# CAN_Sheet.net
KiCad netlist of a schematic drawn in Altium Designer
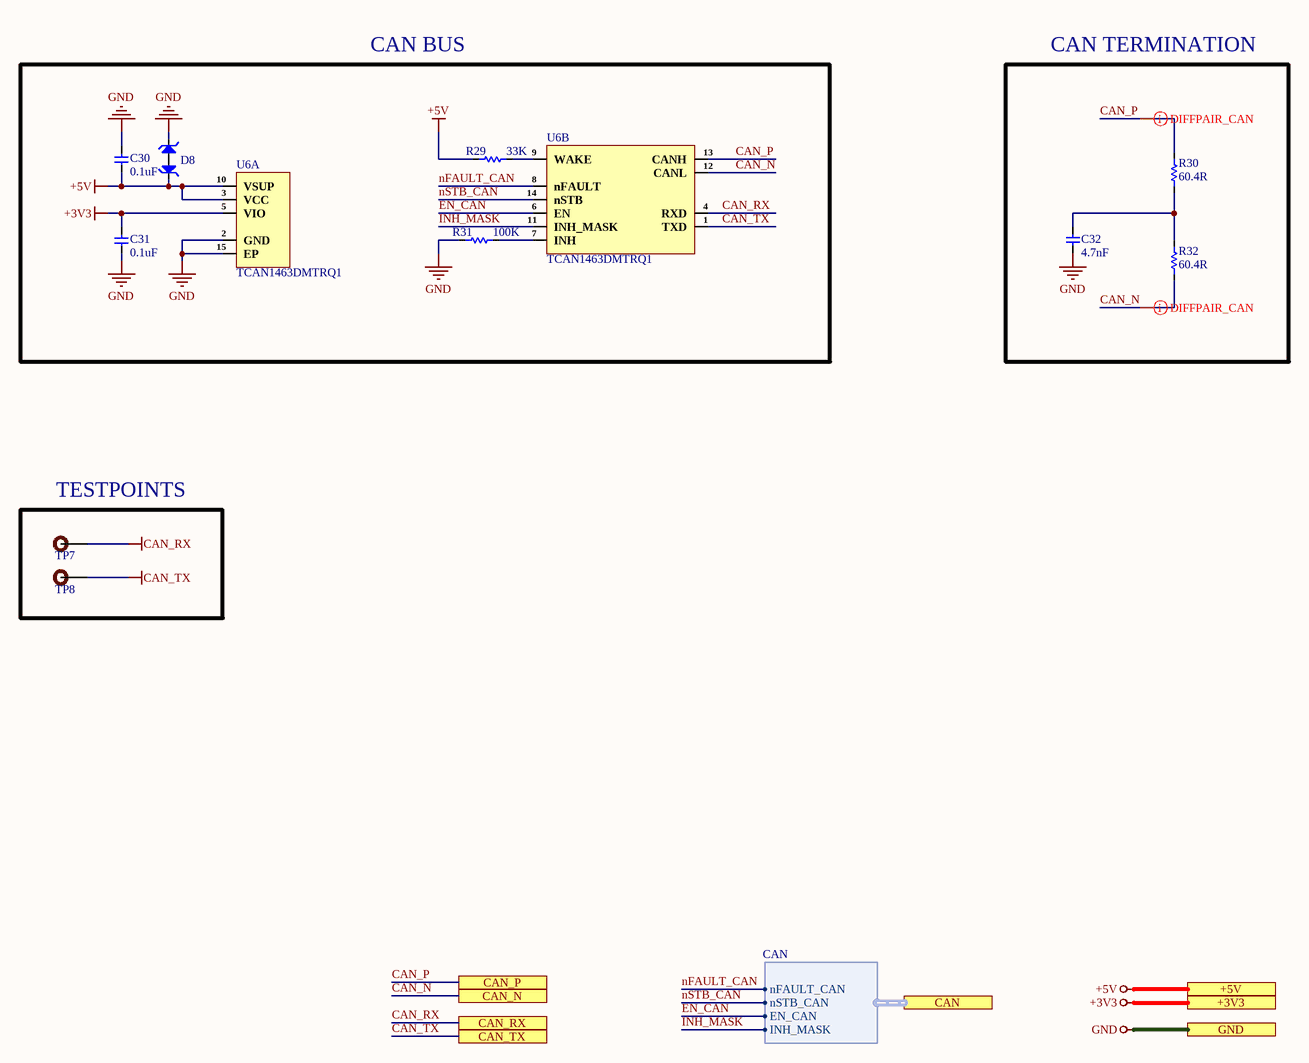
[diagram p0: CAN_Sheet.SchDoc]

(export (version "E")
  (design (tool "Eeschema 10.0.6"))
  (components
    (comp (ref "C30")
      (value "0.1uF")
      (footprint "Cap-0402")
      (description "CAP CER 0.1UF 16V X7R 0402")
      (fields
        (field (name "MANUFACTURER") "Yageo")
        (field (name "MANUFACTURER PART NUMBER") "CC0402JRX7R7BB104")
      )
      (libsource (lib "eSpark Libraries") (part "CC0402JRX7R7BB104"))
    )
    (comp (ref "C31")
      (value "0.1uF")
      (footprint "Cap-0402")
      (description "CAP CER 0.1UF 16V X7R 0402")
      (fields
        (field (name "MANUFACTURER") "Yageo")
        (field (name "MANUFACTURER PART NUMBER") "CC0402JRX7R7BB104")
      )
      (libsource (lib "eSpark Libraries") (part "CC0402JRX7R7BB104"))
    )
    (comp (ref "C32")
      (value "4.7nF")
      (footprint "Cap-0402")
      (description "CAP CER 4700PF 50V X7R 0402")
      (fields
        (field (name "MANUFACTURER") "Yageo")
        (field (name "MANUFACTURER PART NUMBER") "CC0402KRX7R9BB472")
      )
      (libsource (lib "eSpark Libraries") (part "CC0402KRX7R9BB472"))
    )
    (comp (ref "D8")
      (value "PESD5V0H1BSFYL")
      (footprint "DSN0603-2")
      (description "TVS DIODE 5VWM 6.3VC DSN0603-2")
      (fields (field (name "MANUFACTURER") "Nexperia") (field (name "LCSC PART NUMBER") "C477989"))
      (libsource (lib "eSpark Libraries") (part "PESD5V0H1BSFYL"))
    )
    (comp (ref "R29")
      (value "33K")
      (footprint "Res-0402")
      (description "RES 33K OHM 1% 1/16W 0402")
      (fields
        (field (name "MANUFACTURER") "YAGEO")
        (field (name "MANUFACTURER PART NUMBER") "RC0402FR-0733KL")
      )
      (libsource (lib "eSpark Libraries") (part "RC0402FR-0733KL"))
    )
    (comp (ref "R30")
      (value "60.4R")
      (footprint "Res-0603")
      (description "100mW Thick Film Resistors ±100ppm/℃ ±1% 60.4Ω 0603 Chip Resistor - Surface Mount ROHS")
      (fields
        (field (name "MANUFACTURER PART NUMBER") "RTT0360R4FTP")
        (field (name "LCSC PART NUMBER") "C103744")
      )
      (libsource (lib "eSpark Libraries") (part "RTT0360R4FTP"))
    )
    (comp (ref "R31")
      (value "100K")
      (footprint "Res-0402")
      (description "RES 100K OHM 1% 1/16W 0402")
      (fields
        (field (name "MANUFACTURER") "Yageo")
        (field (name "MANUFACTURER PART NUMBER") "RC0402FR-07100KL")
      )
      (libsource (lib "eSpark Libraries") (part "RC0402FR-07100KL"))
    )
    (comp (ref "R32")
      (value "60.4R")
      (footprint "Res-0603")
      (description "100mW Thick Film Resistors ±100ppm/℃ ±1% 60.4Ω 0603 Chip Resistor - Surface Mount ROHS")
      (fields
        (field (name "MANUFACTURER PART NUMBER") "RTT0360R4FTP")
        (field (name "LCSC PART NUMBER") "C103744")
      )
      (libsource (lib "eSpark Libraries") (part "RTT0360R4FTP"))
    )
    (comp (ref "TP7")
      (value "TEST POINT")
      (footprint "Test-point")
      (description "Test Point ON")
      (libsource (lib "eSpark Libraries") (part "TEST POINT"))
    )
    (comp (ref "TP8")
      (value "TEST POINT")
      (footprint "Test-point")
      (description "Test Point ON")
      (libsource (lib "eSpark Libraries") (part "TEST POINT"))
    )
    (comp (ref "U6")
      (value "TCAN1463DMTRQ1")
      (footprint "VSON-14(3x4.5)")
      (description "IC TRANSCEIVER HALF 1/1 14VSON")
      (fields (field (name "MANUFACTURER") "Texas Instruments") (field (name "LCSC PART NUMBER") "C5215823"))
      (libsource (lib "eSpark Libraries") (part "TCAN1463DMTRQ1"))
    )
  )
  (nets
    (net (code "2") (name "+3V3") (class "Default")
      (node (ref "C31") (pin "2") (pinfunction "2_2") (pintype "passive"))
      (node (ref "U6") (pin "5") (pinfunction "VIO_5") (pintype "passive"))
    )
    (net (code "3") (name "+5V") (class "Default")
      (node (ref "C30") (pin "1") (pinfunction "1_1") (pintype "passive"))
      (node (ref "D8") (pin "1") (pinfunction "1_1") (pintype "passive"))
      (node (ref "R29") (pin "1") (pinfunction "1_1") (pintype "passive"))
      (node (ref "U6") (pin "10") (pinfunction "VSUP_10") (pintype "passive"))
      (node (ref "U6") (pin "3") (pinfunction "VCC_3") (pintype "passive"))
    )
    (net (code "4") (name "/CAN_N") (class "Default")
      (node (ref "R32") (pin "2") (pinfunction "2_2") (pintype "passive"))
      (node (ref "U6") (pin "12") (pinfunction "CANL_12") (pintype "passive"))
    )
    (net (code "5") (name "/CAN_P") (class "Default")
      (node (ref "R30") (pin "1") (pinfunction "1_1") (pintype "passive"))
      (node (ref "U6") (pin "13") (pinfunction "CANH_13") (pintype "passive"))
    )
    (net (code "6") (name "/EN_CAN") (class "Default")
      (node (ref "U6") (pin "6") (pinfunction "EN_6") (pintype "passive"))
    )
    (net (code "7") (name "/INH_MASK") (class "Default")
      (node (ref "U6") (pin "11") (pinfunction "INH_MASK_11") (pintype "passive"))
    )
    (net (code "8") (name "/nFAULT_CAN") (class "Default")
      (node (ref "U6") (pin "8") (pinfunction "nFAULT_8") (pintype "passive"))
    )
    (net (code "9") (name "/nSTB_CAN") (class "Default")
      (node (ref "U6") (pin "14") (pinfunction "nSTB_14") (pintype "passive"))
    )
    (net (code "11") (name "CAN_RX") (class "Default")
      (node (ref "TP7") (pin "1") (pinfunction "1_1") (pintype "passive"))
      (node (ref "U6") (pin "4") (pinfunction "RXD_4") (pintype "passive"))
    )
    (net (code "12") (name "CAN_TX") (class "Default")
      (node (ref "TP8") (pin "1") (pinfunction "1_1") (pintype "passive"))
      (node (ref "U6") (pin "1") (pinfunction "TXD_1") (pintype "passive"))
    )
    (net (code "13") (name "GND") (class "Default")
      (node (ref "C30") (pin "2") (pinfunction "2_2") (pintype "passive"))
      (node (ref "C31") (pin "1") (pinfunction "1_1") (pintype "passive"))
      (node (ref "C32") (pin "2") (pinfunction "2_2") (pintype "passive"))
      (node (ref "D8") (pin "2") (pinfunction "2_2") (pintype "passive"))
      (node (ref "R31") (pin "1") (pinfunction "1_1") (pintype "passive"))
      (node (ref "U6") (pin "15") (pinfunction "EP_15") (pintype "passive"))
      (node (ref "U6") (pin "2") (pinfunction "GND_2") (pintype "passive"))
    )
    (net (code "14") (name "Net-(C32-Pad1)") (class "Default")
      (node (ref "C32") (pin "1") (pinfunction "1_1") (pintype "passive"))
      (node (ref "R30") (pin "2") (pinfunction "2_2") (pintype "passive"))
      (node (ref "R32") (pin "1") (pinfunction "1_1") (pintype "passive"))
    )
    (net (code "15") (name "Net-(U6B-INH)") (class "Default")
      (node (ref "R31") (pin "2") (pinfunction "2_2") (pintype "passive"))
      (node (ref "U6") (pin "7") (pinfunction "INH_7") (pintype "passive"))
    )
    (net (code "16") (name "Net-(U6B-WAKE)") (class "Default")
      (node (ref "R29") (pin "2") (pinfunction "2_2") (pintype "passive"))
      (node (ref "U6") (pin "9") (pinfunction "WAKE_9") (pintype "passive"))
    )
  )
)
